# Pendulum_Lamp_PCB.net
KiCad netlist of a schematic drawn in EAGLE
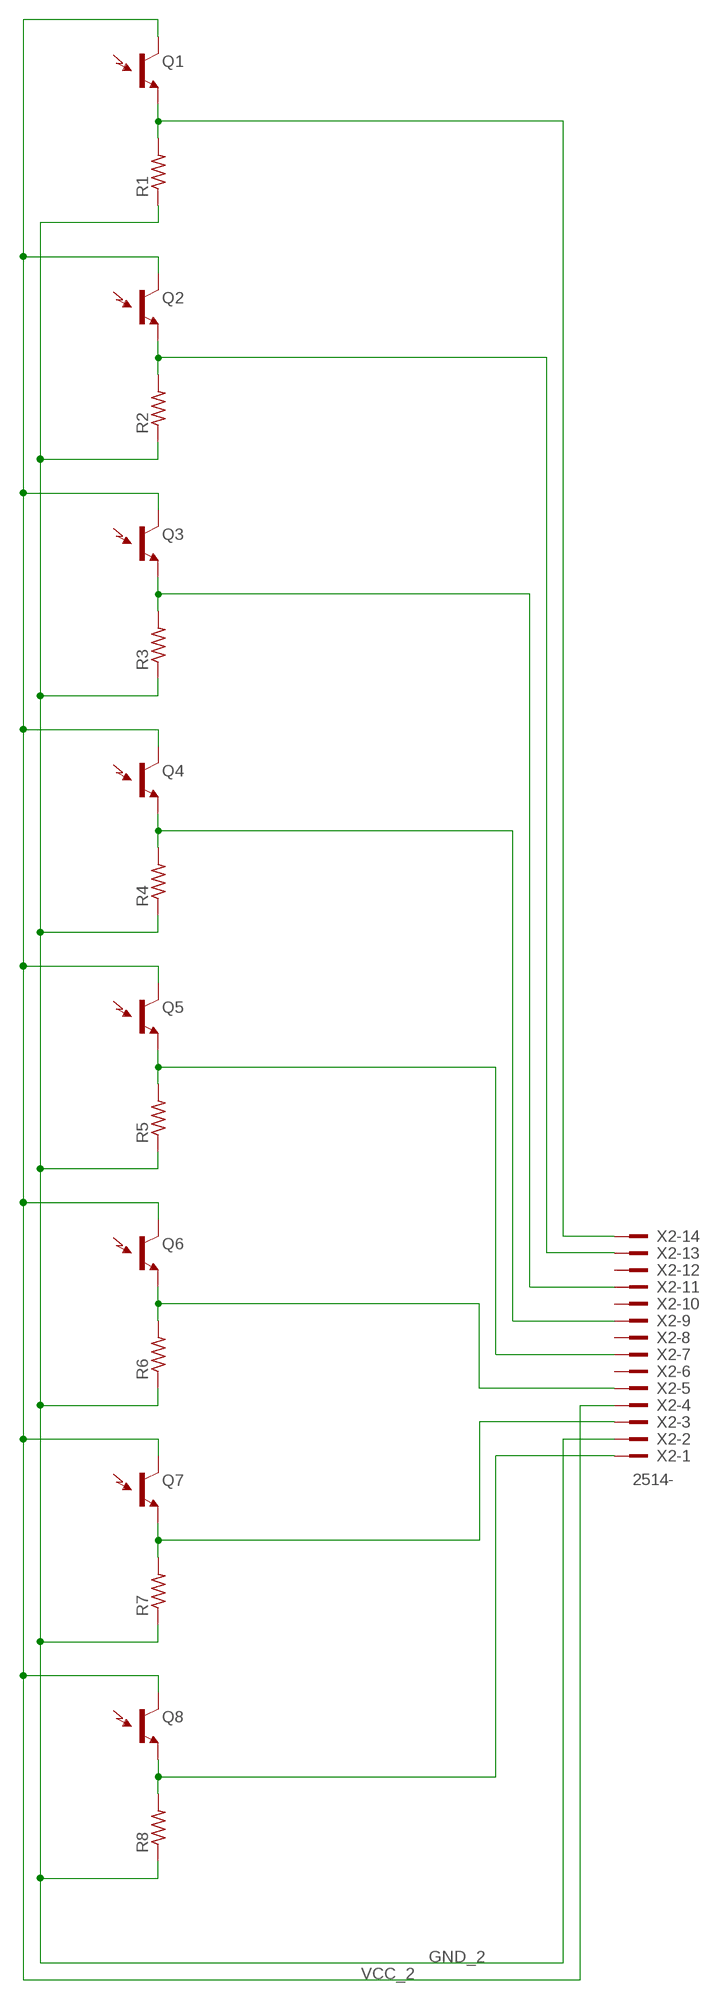
[diagram p0: schematic, sheet 1]

(export (version "E")
  (design (tool "Eeschema 10.0.6"))
  (components
    (comp (ref "Q1")
      (value "LTR-301")
      (footprint "eagle-import:LTR-301")
      (libsource (lib "eagle-import") (part "LTR-301"))
    )
    (comp (ref "Q2")
      (value "LTR-301")
      (footprint "eagle-import:LTR-301")
      (libsource (lib "eagle-import") (part "LTR-301"))
    )
    (comp (ref "Q3")
      (value "LTR-301")
      (footprint "eagle-import:LTR-301")
      (libsource (lib "eagle-import") (part "LTR-301"))
    )
    (comp (ref "Q4")
      (value "LTR-301")
      (footprint "eagle-import:LTR-301")
      (libsource (lib "eagle-import") (part "LTR-301"))
    )
    (comp (ref "Q5")
      (value "LTR-301")
      (footprint "eagle-import:LTR-301")
      (libsource (lib "eagle-import") (part "LTR-301"))
    )
    (comp (ref "Q6")
      (value "LTR-301")
      (footprint "eagle-import:LTR-301")
      (libsource (lib "eagle-import") (part "LTR-301"))
    )
    (comp (ref "Q7")
      (value "LTR-301")
      (footprint "eagle-import:LTR-301")
      (libsource (lib "eagle-import") (part "LTR-301"))
    )
    (comp (ref "Q8")
      (value "LTR-301")
      (footprint "eagle-import:LTR-301")
      (libsource (lib "eagle-import") (part "LTR-301"))
    )
    (comp (ref "R1")
      (value "R-US_0204/7")
      (footprint "eagle-import:0204_7")
      (libsource (lib "eagle-import") (part "R-US_0204/7"))
    )
    (comp (ref "R2")
      (value "R-US_0204/7")
      (footprint "eagle-import:0204_7")
      (libsource (lib "eagle-import") (part "R-US_0204/7"))
    )
    (comp (ref "R3")
      (value "R-US_0204/7")
      (footprint "eagle-import:0204_7")
      (libsource (lib "eagle-import") (part "R-US_0204/7"))
    )
    (comp (ref "R4")
      (value "R-US_0204/7")
      (footprint "eagle-import:0204_7")
      (libsource (lib "eagle-import") (part "R-US_0204/7"))
    )
    (comp (ref "R5")
      (value "R-US_0204/7")
      (footprint "eagle-import:0204_7")
      (libsource (lib "eagle-import") (part "R-US_0204/7"))
    )
    (comp (ref "R6")
      (value "R-US_0204/7")
      (footprint "eagle-import:0204_7")
      (libsource (lib "eagle-import") (part "R-US_0204/7"))
    )
    (comp (ref "R7")
      (value "R-US_0204/7")
      (footprint "eagle-import:0204_7")
      (libsource (lib "eagle-import") (part "R-US_0204/7"))
    )
    (comp (ref "R8")
      (value "R-US_0204/7")
      (footprint "eagle-import:0204_7")
      (libsource (lib "eagle-import") (part "R-US_0204/7"))
    )
    (comp (ref "X2")
      (value "2514-")
      (footprint "eagle-import:PAK100_2500-14")
      (libsource (lib "eagle-import") (part "2514-"))
    )
  )
  (nets
    (net (code "1") (name "/GND_2") (class "Default")
      (node (ref "R1") (pin "1") (pinfunction "1_1") (pintype "passive"))
      (node (ref "R2") (pin "1") (pinfunction "1_1") (pintype "passive"))
      (node (ref "R3") (pin "1") (pinfunction "1_1") (pintype "passive"))
      (node (ref "R4") (pin "1") (pinfunction "1_1") (pintype "passive"))
      (node (ref "R5") (pin "1") (pinfunction "1_1") (pintype "passive"))
      (node (ref "R6") (pin "1") (pinfunction "1_1") (pintype "passive"))
      (node (ref "R7") (pin "1") (pinfunction "1_1") (pintype "passive"))
      (node (ref "R8") (pin "1") (pinfunction "1_1") (pintype "passive"))
      (node (ref "X2") (pin "2") (pinfunction "KL_2") (pintype "passive"))
    )
    (net (code "2") (name "/VCC_2") (class "Default")
      (node (ref "Q1") (pin "C") (pinfunction "C1_C") (pintype "passive"))
      (node (ref "Q2") (pin "C") (pinfunction "C1_C") (pintype "passive"))
      (node (ref "Q3") (pin "C") (pinfunction "C1_C") (pintype "passive"))
      (node (ref "Q4") (pin "C") (pinfunction "C1_C") (pintype "passive"))
      (node (ref "Q5") (pin "C") (pinfunction "C1_C") (pintype "passive"))
      (node (ref "Q6") (pin "C") (pinfunction "C1_C") (pintype "passive"))
      (node (ref "Q7") (pin "C") (pinfunction "C1_C") (pintype "passive"))
      (node (ref "Q8") (pin "C") (pinfunction "C1_C") (pintype "passive"))
      (node (ref "X2") (pin "4") (pinfunction "KL_4") (pintype "passive"))
    )
    (net (code "3") (name "Net-(Q1-E1)") (class "Default")
      (node (ref "Q1") (pin "E") (pinfunction "E1_E") (pintype "passive"))
      (node (ref "R1") (pin "2") (pinfunction "2_2") (pintype "passive"))
      (node (ref "X2") (pin "14") (pinfunction "KL_14") (pintype "passive"))
    )
    (net (code "4") (name "Net-(Q2-E1)") (class "Default")
      (node (ref "Q2") (pin "E") (pinfunction "E1_E") (pintype "passive"))
      (node (ref "R2") (pin "2") (pinfunction "2_2") (pintype "passive"))
      (node (ref "X2") (pin "13") (pinfunction "KL_13") (pintype "passive"))
    )
    (net (code "5") (name "Net-(Q3-E1)") (class "Default")
      (node (ref "Q3") (pin "E") (pinfunction "E1_E") (pintype "passive"))
      (node (ref "R3") (pin "2") (pinfunction "2_2") (pintype "passive"))
      (node (ref "X2") (pin "11") (pinfunction "KL_11") (pintype "passive"))
    )
    (net (code "6") (name "Net-(Q4-E1)") (class "Default")
      (node (ref "Q4") (pin "E") (pinfunction "E1_E") (pintype "passive"))
      (node (ref "R4") (pin "2") (pinfunction "2_2") (pintype "passive"))
      (node (ref "X2") (pin "9") (pinfunction "KL_9") (pintype "passive"))
    )
    (net (code "7") (name "Net-(Q5-E1)") (class "Default")
      (node (ref "Q5") (pin "E") (pinfunction "E1_E") (pintype "passive"))
      (node (ref "R5") (pin "2") (pinfunction "2_2") (pintype "passive"))
      (node (ref "X2") (pin "7") (pinfunction "KL_7") (pintype "passive"))
    )
    (net (code "8") (name "Net-(Q6-E1)") (class "Default")
      (node (ref "Q6") (pin "E") (pinfunction "E1_E") (pintype "passive"))
      (node (ref "R6") (pin "2") (pinfunction "2_2") (pintype "passive"))
      (node (ref "X2") (pin "5") (pinfunction "KL_5") (pintype "passive"))
    )
    (net (code "9") (name "Net-(Q7-E1)") (class "Default")
      (node (ref "Q7") (pin "E") (pinfunction "E1_E") (pintype "passive"))
      (node (ref "R7") (pin "2") (pinfunction "2_2") (pintype "passive"))
      (node (ref "X2") (pin "3") (pinfunction "KL_3") (pintype "passive"))
    )
    (net (code "10") (name "Net-(Q8-E1)") (class "Default")
      (node (ref "Q8") (pin "E") (pinfunction "E1_E") (pintype "passive"))
      (node (ref "R8") (pin "2") (pinfunction "2_2") (pintype "passive"))
      (node (ref "X2") (pin "1") (pinfunction "KL_1") (pintype "passive"))
    )
    (net (code "11") (name "unconnected-(X2B-KL-Pad10)") (class "Default")
      (node (ref "X2") (pin "10") (pinfunction "KL_10") (pintype "passive"))
    )
    (net (code "12") (name "unconnected-(X2D-KL-Pad12)") (class "Default")
      (node (ref "X2") (pin "12") (pinfunction "KL_12") (pintype "passive"))
    )
    (net (code "13") (name "unconnected-(X2K-KL-Pad6)") (class "Default")
      (node (ref "X2") (pin "6") (pinfunction "KL_6") (pintype "passive"))
    )
    (net (code "14") (name "unconnected-(X2M-KL-Pad8)") (class "Default")
      (node (ref "X2") (pin "8") (pinfunction "KL_8") (pintype "passive"))
    )
  )
)
